# Dual_Z.net
KiCad netlist of a schematic drawn in Altium Designer
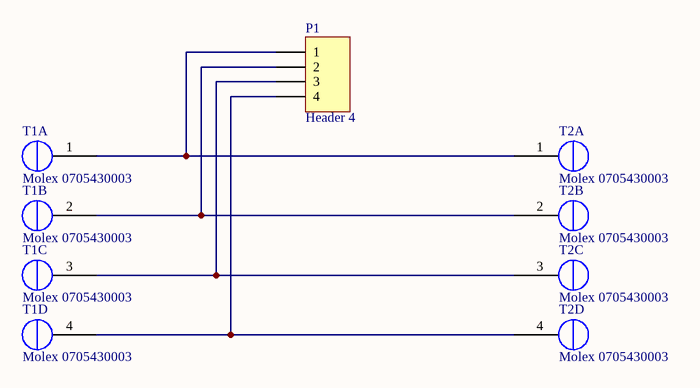
[diagram p0: Dual Z.SchDoc]

(export (version "E")
  (design (tool "Eeschema 10.0.6"))
  (components
    (comp (ref "P1")
      (value "Header 4")
      (footprint "HDR1X4")
      (description "Header, 4-Pin")
      (fields (field (name "PUBLISHER") "Altium Limited"))
      (libsource (lib "Miscellaneous Connectors") (part "Header 4"))
    )
    (comp (ref "T1")
      (value "Molex 0705430003")
      (footprint "Molex 0705430003")
      (description "Molex 4 Pin Clip Connector")
      (libsource (lib "") (part "Molex 0705430003 Alt_4"))
    )
    (comp (ref "T2")
      (value "Molex 0705430003")
      (footprint "Molex 0705430003")
      (description "Molex 4 Pin Clip Connector")
      (libsource (lib "") (part "Molex 0705430003 Alt_1"))
    )
  )
  (nets
    (net (code "1") (name "Net-(T1A-OUT2B)") (class "Default")
      (node (ref "P1") (pin "1") (pinfunction "1_1") (pintype "passive"))
      (node (ref "T1") (pin "1") (pinfunction "OUT2B_1") (pintype "passive"))
      (node (ref "T2") (pin "1") (pinfunction "OUT2B_1") (pintype "passive"))
    )
    (net (code "2") (name "Net-(T1B-OUT2A)") (class "Default")
      (node (ref "P1") (pin "2") (pinfunction "2_2") (pintype "passive"))
      (node (ref "T1") (pin "2") (pinfunction "OUT2A_2") (pintype "passive"))
      (node (ref "T2") (pin "2") (pinfunction "OUT2A_2") (pintype "passive"))
    )
    (net (code "3") (name "Net-(T1C-OUT1A)") (class "Default")
      (node (ref "P1") (pin "3") (pinfunction "3_3") (pintype "passive"))
      (node (ref "T1") (pin "3") (pinfunction "OUT1A_3") (pintype "passive"))
      (node (ref "T2") (pin "3") (pinfunction "OUT1A_3") (pintype "passive"))
    )
    (net (code "4") (name "Net-(T1D-OUT1B)") (class "Default")
      (node (ref "P1") (pin "4") (pinfunction "4_4") (pintype "passive"))
      (node (ref "T1") (pin "4") (pinfunction "OUT1B_4") (pintype "passive"))
      (node (ref "T2") (pin "4") (pinfunction "OUT1B_4") (pintype "passive"))
    )
  )
)
